# 2_RK3399_SDRAM.net
KiCad netlist of a schematic drawn in Altium Designer
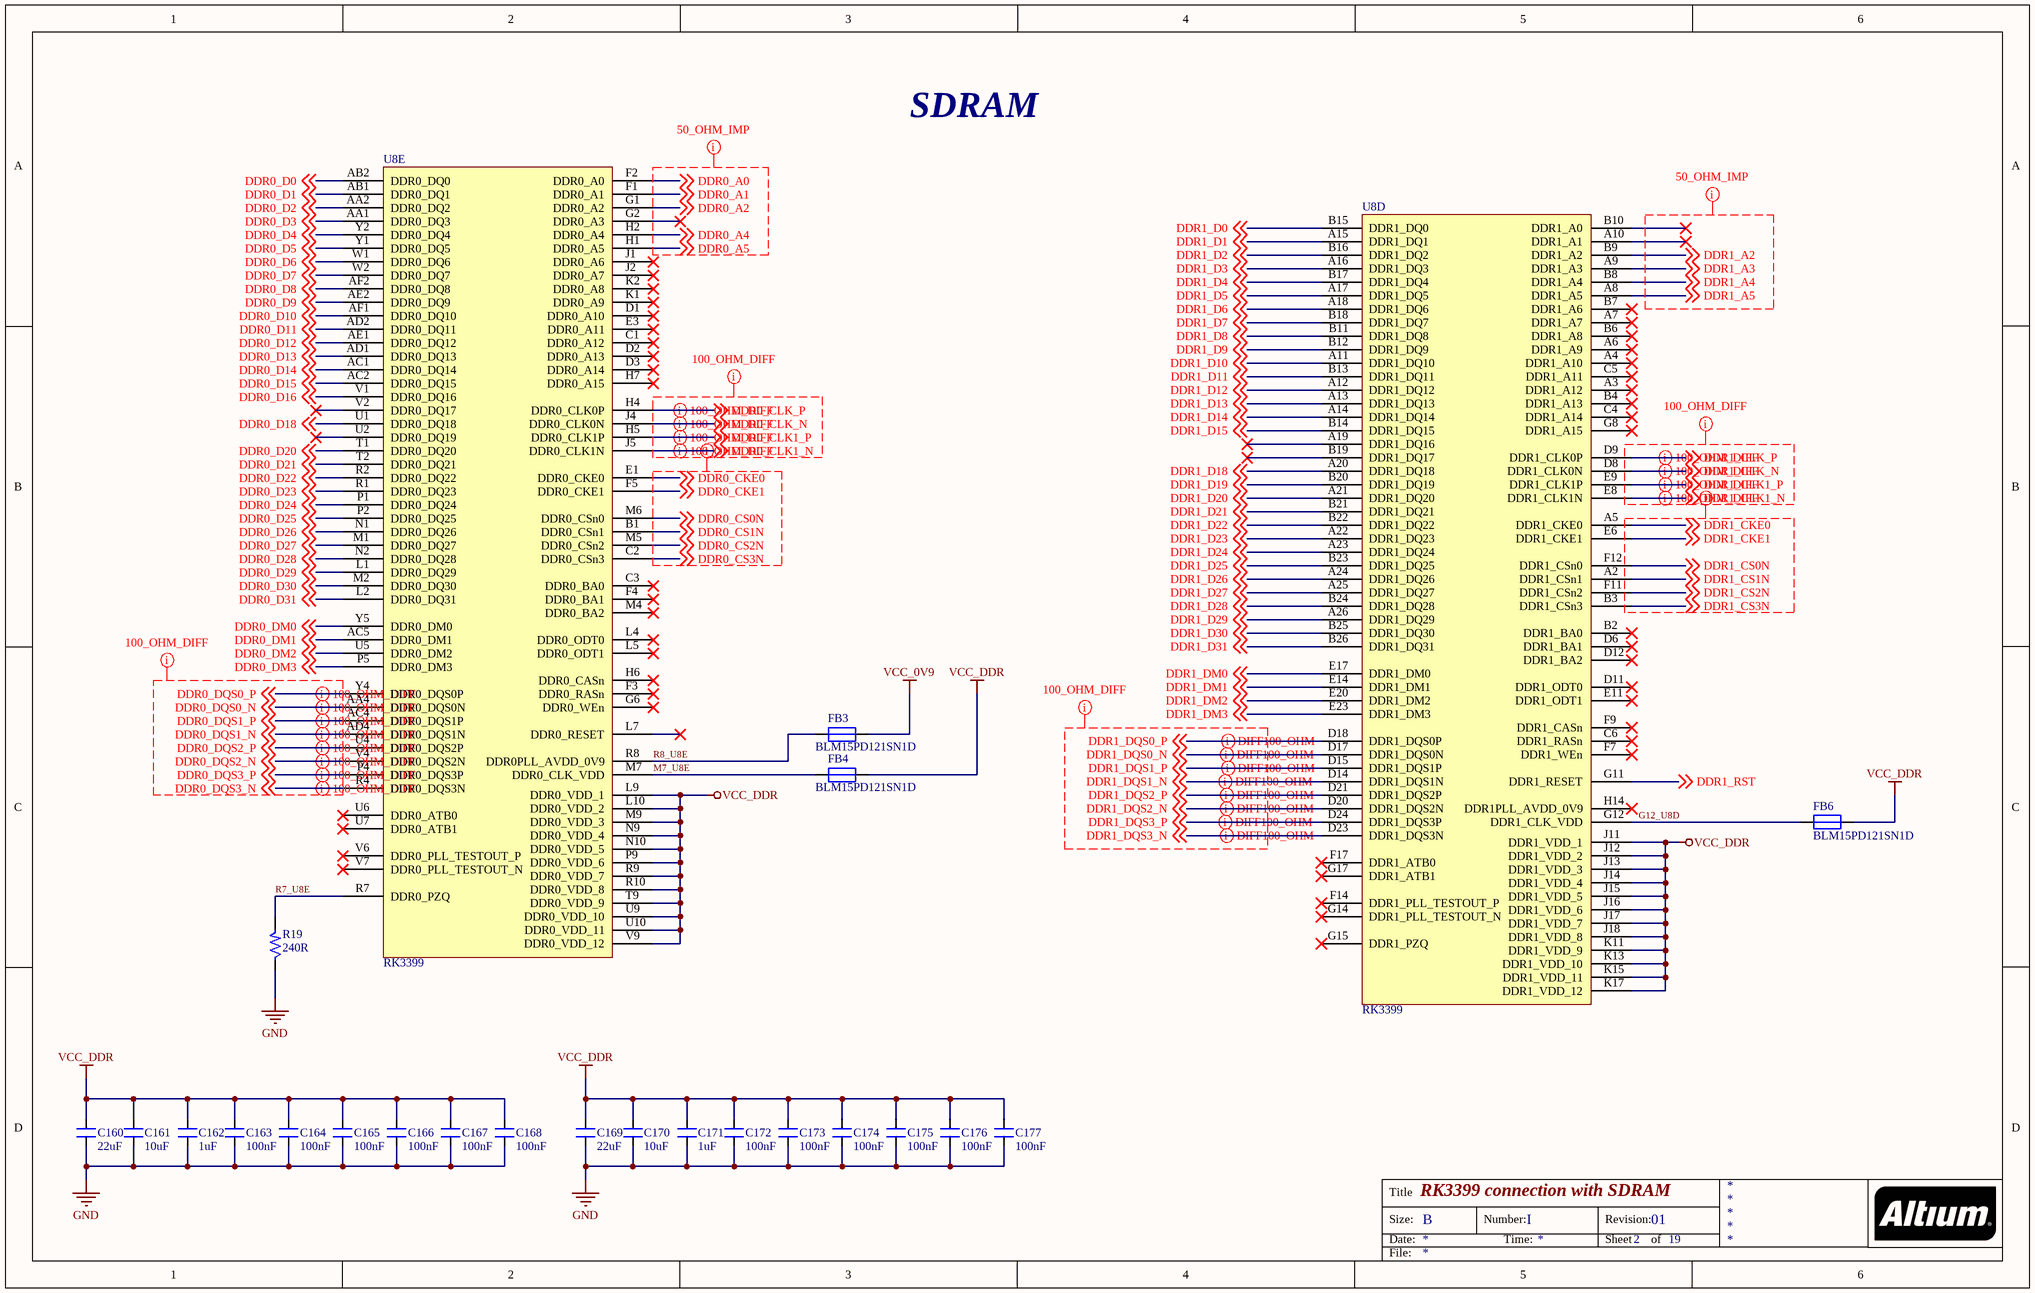
[diagram p0: [2] RK3399_SDRAM.SchDoc]

(export (version "E")
  (design (tool "Eeschema 10.0.6"))
  (components
    (comp (ref "C160")
      (value "22uF")
      (footprint "CAP_0402")
      (description "22µF ±20% 6.3V Ceramic Capacitor X5R 0402 (1005 Metric)")
      (fields
        (field (name "MANUFACTURER") "Murata Electronics")
        (field (name "MANUFACTURER PART NUMBER") "CL05A226MQ5N6J8")
      )
      (libsource (lib "EsteemPCB_SOM_Course_intlib") (part "CAP_22uF-6.3V-20%-0402"))
    )
    (comp (ref "C161")
      (value "10uF")
      (footprint "CAP_0402")
      (description "10µF ±20% 10V Ceramic Capacitor X5R 0402 (1005 Metric)")
      (fields
        (field (name "MANUFACTURER PART NUMBER") "CL05A106MP5NUNC")
        (field (name "MANUFACTURER") "Samsung Electro-Mechanics")
      )
      (libsource (lib "EsteemPCB_SOM_Course_intlib") (part "CAP_10uF-10V-20%-0402"))
    )
    (comp (ref "C162")
      (value "1uF")
      (footprint "CAP_0402")
      (description "1µF ±10% 10V Ceramic Capacitor X6S 0402 (1005 Metric)")
      (fields
        (field (name "MANUFACTURER") "Murata Electronics")
        (field (name "MANUFACTURER PART NUMBER") "GRT155C81A105KE01D")
      )
      (libsource (lib "EsteemPCB_SOM_Course_intlib") (part "CAP_1uF-10V-10%-0402"))
    )
    (comp (ref "C163")
      (value "100nF")
      (footprint "CAP_0402")
      (description "0.1µF ±10% 10V Ceramic Capacitor X7R 0402 (1005 Metric)")
      (fields
        (field (name "MANUFACTURER") "Yageo")
        (field (name "MANUFACTURER PART NUMBER") "CC0402KRX7R6BB104")
      )
      (libsource (lib "EsteemPCB_SOM_Course_intlib") (part "CAP_100nF-10V-10%-0402"))
    )
    (comp (ref "C164")
      (value "100nF")
      (footprint "CAP_0402")
      (description "0.1µF ±10% 10V Ceramic Capacitor X7R 0402 (1005 Metric)")
      (fields
        (field (name "MANUFACTURER") "Yageo")
        (field (name "MANUFACTURER PART NUMBER") "CC0402KRX7R6BB104")
      )
      (libsource (lib "EsteemPCB_SOM_Course_intlib") (part "CAP_100nF-10V-10%-0402"))
    )
    (comp (ref "C165")
      (value "100nF")
      (footprint "CAP_0402")
      (description "0.1µF ±10% 10V Ceramic Capacitor X7R 0402 (1005 Metric)")
      (fields
        (field (name "MANUFACTURER") "Yageo")
        (field (name "MANUFACTURER PART NUMBER") "CC0402KRX7R6BB104")
      )
      (libsource (lib "EsteemPCB_SOM_Course_intlib") (part "CAP_100nF-10V-10%-0402"))
    )
    (comp (ref "C166")
      (value "100nF")
      (footprint "CAP_0402")
      (description "0.1µF ±10% 10V Ceramic Capacitor X7R 0402 (1005 Metric)")
      (fields
        (field (name "MANUFACTURER") "Yageo")
        (field (name "MANUFACTURER PART NUMBER") "CC0402KRX7R6BB104")
      )
      (libsource (lib "EsteemPCB_SOM_Course_intlib") (part "CAP_100nF-10V-10%-0402"))
    )
    (comp (ref "C167")
      (value "100nF")
      (footprint "CAP_0402")
      (description "0.1µF ±10% 10V Ceramic Capacitor X7R 0402 (1005 Metric)")
      (fields
        (field (name "MANUFACTURER") "Yageo")
        (field (name "MANUFACTURER PART NUMBER") "CC0402KRX7R6BB104")
      )
      (libsource (lib "EsteemPCB_SOM_Course_intlib") (part "CAP_100nF-10V-10%-0402"))
    )
    (comp (ref "C168")
      (value "100nF")
      (footprint "CAP_0402")
      (description "0.1µF ±10% 10V Ceramic Capacitor X7R 0402 (1005 Metric)")
      (fields
        (field (name "MANUFACTURER") "Yageo")
        (field (name "MANUFACTURER PART NUMBER") "CC0402KRX7R6BB104")
      )
      (libsource (lib "EsteemPCB_SOM_Course_intlib") (part "CAP_100nF-10V-10%-0402"))
    )
    (comp (ref "C169")
      (value "22uF")
      (footprint "CAP_0402")
      (description "22µF ±20% 6.3V Ceramic Capacitor X5R 0402 (1005 Metric)")
      (fields
        (field (name "MANUFACTURER") "Murata Electronics")
        (field (name "MANUFACTURER PART NUMBER") "CL05A226MQ5N6J8")
      )
      (libsource (lib "EsteemPCB_SOM_Course_intlib") (part "CAP_22uF-6.3V-20%-0402"))
    )
    (comp (ref "C170")
      (value "10uF")
      (footprint "CAP_0402")
      (description "10µF ±20% 10V Ceramic Capacitor X5R 0402 (1005 Metric)")
      (fields
        (field (name "MANUFACTURER PART NUMBER") "CL05A106MP5NUNC")
        (field (name "MANUFACTURER") "Samsung Electro-Mechanics")
      )
      (libsource (lib "EsteemPCB_SOM_Course_intlib") (part "CAP_10uF-10V-20%-0402"))
    )
    (comp (ref "C171")
      (value "1uF")
      (footprint "CAP_0402")
      (description "1µF ±10% 10V Ceramic Capacitor X6S 0402 (1005 Metric)")
      (fields
        (field (name "MANUFACTURER") "Murata Electronics")
        (field (name "MANUFACTURER PART NUMBER") "GRT155C81A105KE01D")
      )
      (libsource (lib "EsteemPCB_SOM_Course_intlib") (part "CAP_1uF-10V-10%-0402"))
    )
    (comp (ref "C172")
      (value "100nF")
      (footprint "CAP_0402")
      (description "0.1µF ±10% 10V Ceramic Capacitor X7R 0402 (1005 Metric)")
      (fields
        (field (name "MANUFACTURER") "Yageo")
        (field (name "MANUFACTURER PART NUMBER") "CC0402KRX7R6BB104")
      )
      (libsource (lib "EsteemPCB_SOM_Course_intlib") (part "CAP_100nF-10V-10%-0402"))
    )
    (comp (ref "C173")
      (value "100nF")
      (footprint "CAP_0402")
      (description "0.1µF ±10% 10V Ceramic Capacitor X7R 0402 (1005 Metric)")
      (fields
        (field (name "MANUFACTURER") "Yageo")
        (field (name "MANUFACTURER PART NUMBER") "CC0402KRX7R6BB104")
      )
      (libsource (lib "EsteemPCB_SOM_Course_intlib") (part "CAP_100nF-10V-10%-0402"))
    )
    (comp (ref "C174")
      (value "100nF")
      (footprint "CAP_0402")
      (description "0.1µF ±10% 10V Ceramic Capacitor X7R 0402 (1005 Metric)")
      (fields
        (field (name "MANUFACTURER") "Yageo")
        (field (name "MANUFACTURER PART NUMBER") "CC0402KRX7R6BB104")
      )
      (libsource (lib "EsteemPCB_SOM_Course_intlib") (part "CAP_100nF-10V-10%-0402"))
    )
    (comp (ref "C175")
      (value "100nF")
      (footprint "CAP_0402")
      (description "0.1µF ±10% 10V Ceramic Capacitor X7R 0402 (1005 Metric)")
      (fields
        (field (name "MANUFACTURER") "Yageo")
        (field (name "MANUFACTURER PART NUMBER") "CC0402KRX7R6BB104")
      )
      (libsource (lib "EsteemPCB_SOM_Course_intlib") (part "CAP_100nF-10V-10%-0402"))
    )
    (comp (ref "C176")
      (value "100nF")
      (footprint "CAP_0402")
      (description "0.1µF ±10% 10V Ceramic Capacitor X7R 0402 (1005 Metric)")
      (fields
        (field (name "MANUFACTURER") "Yageo")
        (field (name "MANUFACTURER PART NUMBER") "CC0402KRX7R6BB104")
      )
      (libsource (lib "EsteemPCB_SOM_Course_intlib") (part "CAP_100nF-10V-10%-0402"))
    )
    (comp (ref "C177")
      (value "100nF")
      (footprint "CAP_0402")
      (description "0.1µF ±10% 10V Ceramic Capacitor X7R 0402 (1005 Metric)")
      (fields
        (field (name "MANUFACTURER") "Yageo")
        (field (name "MANUFACTURER PART NUMBER") "CC0402KRX7R6BB104")
      )
      (libsource (lib "EsteemPCB_SOM_Course_intlib") (part "CAP_100nF-10V-10%-0402"))
    )
    (comp (ref "FB3")
      (value "BLM15PD121SN1D")
      (footprint "RES_0402")
      (description "120 Ohms @ 100MHz 1 Power Line Ferrite Bead 0402 (1005 Metric) 1.3A 90mOhm")
      (fields (field (name "MANUFACTURER") "Murata Electronics"))
      (libsource (lib "EsteemPCB_SOM_Course_intlib") (part "FB_120R-1.3A-100Mhz-0402"))
    )
    (comp (ref "FB4")
      (value "BLM15PD121SN1D")
      (footprint "RES_0402")
      (description "120 Ohms @ 100MHz 1 Power Line Ferrite Bead 0402 (1005 Metric) 1.3A 90mOhm")
      (fields (field (name "MANUFACTURER") "Murata Electronics"))
      (libsource (lib "EsteemPCB_SOM_Course_intlib") (part "FB_120R-1.3A-100Mhz-0402"))
    )
    (comp (ref "FB6")
      (value "BLM15PD121SN1D")
      (footprint "RES_0402")
      (description "120 Ohms @ 100MHz 1 Power Line Ferrite Bead 0402 (1005 Metric) 1.3A 90mOhm")
      (fields (field (name "MANUFACTURER") "Murata Electronics"))
      (libsource (lib "EsteemPCB_SOM_Course_intlib") (part "FB_120R-1.3A-100Mhz-0402"))
    )
    (comp (ref "R19")
      (value "240R")
      (footprint "RES_0201")
      (description "240 Ohms ±1% 0.05W, 1/20W Chip Resistor 0201 (0603 Metric) Thick Film")
      (fields
        (field (name "MANUFACTURER") "Yageo")
        (field (name "MANUFACTURER PART NUMBER") "RC0201FR-07240RL")
      )
      (libsource (lib "EsteemPCB_SOM_Course_intlib") (part "RES_240R-0.05W-1%-0201"))
    )
    (comp (ref "U8")
      (value "RK3399")
      (footprint "FBGA828_23_826X826")
      (description "RK3399 is a low power, high performance processor for computing, personal mobile.")
      (fields (field (name "MANUFACTURER") "Rockchip"))
      (libsource (lib "EsteemPCB_SOM_Course_intlib") (part "IC_RK3399-FCBGA828"))
    )
  )
  (nets
    (net (code "1") (name "/G12_U8D") (class "Default")
      (node (ref "FB6") (pin "1") (pinfunction "1_1") (pintype "passive"))
      (node (ref "U8") (pin "G12") (pinfunction "DDR1_CLK_VDD_G12") (pintype "passive"))
    )
    (net (code "2") (name "/M7_U8E") (class "Default")
      (node (ref "FB4") (pin "1") (pinfunction "1_1") (pintype "passive"))
      (node (ref "U8") (pin "M7") (pinfunction "DDR0_CLK_VDD_M7") (pintype "passive"))
    )
    (net (code "3") (name "/R7_U8E") (class "Default")
      (node (ref "R19") (pin "2") (pinfunction "2_2") (pintype "passive"))
      (node (ref "U8") (pin "R7") (pinfunction "DDR0_PZQ_R7") (pintype "passive"))
    )
    (net (code "4") (name "/R8_U8E") (class "Default")
      (node (ref "FB3") (pin "1") (pinfunction "1_1") (pintype "passive"))
      (node (ref "U8") (pin "R8") (pinfunction "DDR0PLL_AVDD_0V9_R8") (pintype "passive"))
    )
    (net (code "5") (name "DDR0_A0") (class "Default")
      (node (ref "U8") (pin "F2") (pinfunction "DDR0_A0_F2") (pintype "passive"))
    )
    (net (code "6") (name "DDR0_A1") (class "Default")
      (node (ref "U8") (pin "F1") (pinfunction "DDR0_A1_F1") (pintype "passive"))
    )
    (net (code "7") (name "DDR0_A2") (class "Default")
      (node (ref "U8") (pin "G1") (pinfunction "DDR0_A2_G1") (pintype "passive"))
    )
    (net (code "8") (name "DDR0_A4") (class "Default")
      (node (ref "U8") (pin "H2") (pinfunction "DDR0_A4_H2") (pintype "passive"))
    )
    (net (code "9") (name "DDR0_A5") (class "Default")
      (node (ref "U8") (pin "H1") (pinfunction "DDR0_A5_H1") (pintype "passive"))
    )
    (net (code "10") (name "DDR0_CKE0") (class "Default")
      (node (ref "U8") (pin "E1") (pinfunction "DDR0_CKE0_E1") (pintype "passive"))
    )
    (net (code "11") (name "DDR0_CKE1") (class "Default")
      (node (ref "U8") (pin "F5") (pinfunction "DDR0_CKE1_F5") (pintype "passive"))
    )
    (net (code "12") (name "DDR0_CLK1_N") (class "Default")
      (node (ref "U8") (pin "J5") (pinfunction "DDR0_CLK1N_J5") (pintype "passive"))
    )
    (net (code "13") (name "DDR0_CLK1_P") (class "Default")
      (node (ref "U8") (pin "H5") (pinfunction "DDR0_CLK1P_H5") (pintype "passive"))
    )
    (net (code "14") (name "DDR0_CLK_N") (class "Default")
      (node (ref "U8") (pin "J4") (pinfunction "DDR0_CLK0N_J4") (pintype "passive"))
    )
    (net (code "15") (name "DDR0_CLK_P") (class "Default")
      (node (ref "U8") (pin "H4") (pinfunction "DDR0_CLK0P_H4") (pintype "passive"))
    )
    (net (code "16") (name "DDR0_CS0N") (class "Default")
      (node (ref "U8") (pin "M6") (pinfunction "DDR0_CSn0_M6") (pintype "passive"))
    )
    (net (code "17") (name "DDR0_CS1N") (class "Default")
      (node (ref "U8") (pin "B1") (pinfunction "DDR0_CSn1_B1") (pintype "passive"))
    )
    (net (code "18") (name "DDR0_CS2N") (class "Default")
      (node (ref "U8") (pin "M5") (pinfunction "DDR0_CSn2_M5") (pintype "passive"))
    )
    (net (code "19") (name "DDR0_CS3N") (class "Default")
      (node (ref "U8") (pin "C2") (pinfunction "DDR0_CSn3_C2") (pintype "passive"))
    )
    (net (code "20") (name "DDR0_D0") (class "Default")
      (node (ref "U8") (pin "AB2") (pinfunction "DDR0_DQ0_AB2") (pintype "passive"))
    )
    (net (code "21") (name "DDR0_D1") (class "Default")
      (node (ref "U8") (pin "AB1") (pinfunction "DDR0_DQ1_AB1") (pintype "passive"))
    )
    (net (code "22") (name "DDR0_D2") (class "Default")
      (node (ref "U8") (pin "AA2") (pinfunction "DDR0_DQ2_AA2") (pintype "passive"))
    )
    (net (code "23") (name "DDR0_D3") (class "Default")
      (node (ref "U8") (pin "AA1") (pinfunction "DDR0_DQ3_AA1") (pintype "passive"))
    )
    (net (code "24") (name "DDR0_D4") (class "Default")
      (node (ref "U8") (pin "Y2") (pinfunction "DDR0_DQ4_Y2") (pintype "passive"))
    )
    (net (code "25") (name "DDR0_D5") (class "Default")
      (node (ref "U8") (pin "Y1") (pinfunction "DDR0_DQ5_Y1") (pintype "passive"))
    )
    (net (code "26") (name "DDR0_D6") (class "Default")
      (node (ref "U8") (pin "W1") (pinfunction "DDR0_DQ6_W1") (pintype "passive"))
    )
    (net (code "27") (name "DDR0_D7") (class "Default")
      (node (ref "U8") (pin "W2") (pinfunction "DDR0_DQ7_W2") (pintype "passive"))
    )
    (net (code "28") (name "DDR0_D8") (class "Default")
      (node (ref "U8") (pin "AF2") (pinfunction "DDR0_DQ8_AF2") (pintype "passive"))
    )
    (net (code "29") (name "DDR0_D9") (class "Default")
      (node (ref "U8") (pin "AE2") (pinfunction "DDR0_DQ9_AE2") (pintype "passive"))
    )
    (net (code "30") (name "DDR0_D10") (class "Default")
      (node (ref "U8") (pin "AF1") (pinfunction "DDR0_DQ10_AF1") (pintype "passive"))
    )
    (net (code "31") (name "DDR0_D11") (class "Default")
      (node (ref "U8") (pin "AD2") (pinfunction "DDR0_DQ11_AD2") (pintype "passive"))
    )
    (net (code "32") (name "DDR0_D12") (class "Default")
      (node (ref "U8") (pin "AE1") (pinfunction "DDR0_DQ12_AE1") (pintype "passive"))
    )
    (net (code "33") (name "DDR0_D13") (class "Default")
      (node (ref "U8") (pin "AD1") (pinfunction "DDR0_DQ13_AD1") (pintype "passive"))
    )
    (net (code "34") (name "DDR0_D14") (class "Default")
      (node (ref "U8") (pin "AC1") (pinfunction "DDR0_DQ14_AC1") (pintype "passive"))
    )
    (net (code "35") (name "DDR0_D15") (class "Default")
      (node (ref "U8") (pin "AC2") (pinfunction "DDR0_DQ15_AC2") (pintype "passive"))
    )
    (net (code "36") (name "DDR0_D16") (class "Default")
      (node (ref "U8") (pin "V1") (pinfunction "DDR0_DQ16_V1") (pintype "passive"))
    )
    (net (code "37") (name "DDR0_D18") (class "Default")
      (node (ref "U8") (pin "U1") (pinfunction "DDR0_DQ18_U1") (pintype "passive"))
    )
    (net (code "38") (name "DDR0_D20") (class "Default")
      (node (ref "U8") (pin "T1") (pinfunction "DDR0_DQ20_T1") (pintype "passive"))
    )
    (net (code "39") (name "DDR0_D21") (class "Default")
      (node (ref "U8") (pin "T2") (pinfunction "DDR0_DQ21_T2") (pintype "passive"))
    )
    (net (code "40") (name "DDR0_D22") (class "Default")
      (node (ref "U8") (pin "R2") (pinfunction "DDR0_DQ22_R2") (pintype "passive"))
    )
    (net (code "41") (name "DDR0_D23") (class "Default")
      (node (ref "U8") (pin "R1") (pinfunction "DDR0_DQ23_R1") (pintype "passive"))
    )
    (net (code "42") (name "DDR0_D24") (class "Default")
      (node (ref "U8") (pin "P1") (pinfunction "DDR0_DQ24_P1") (pintype "passive"))
    )
    (net (code "43") (name "DDR0_D25") (class "Default")
      (node (ref "U8") (pin "P2") (pinfunction "DDR0_DQ25_P2") (pintype "passive"))
    )
    (net (code "44") (name "DDR0_D26") (class "Default")
      (node (ref "U8") (pin "N1") (pinfunction "DDR0_DQ26_N1") (pintype "passive"))
    )
    (net (code "45") (name "DDR0_D27") (class "Default")
      (node (ref "U8") (pin "M1") (pinfunction "DDR0_DQ27_M1") (pintype "passive"))
    )
    (net (code "46") (name "DDR0_D28") (class "Default")
      (node (ref "U8") (pin "N2") (pinfunction "DDR0_DQ28_N2") (pintype "passive"))
    )
    (net (code "47") (name "DDR0_D29") (class "Default")
      (node (ref "U8") (pin "L1") (pinfunction "DDR0_DQ29_L1") (pintype "passive"))
    )
    (net (code "48") (name "DDR0_D30") (class "Default")
      (node (ref "U8") (pin "M2") (pinfunction "DDR0_DQ30_M2") (pintype "passive"))
    )
    (net (code "49") (name "DDR0_D31") (class "Default")
      (node (ref "U8") (pin "L2") (pinfunction "DDR0_DQ31_L2") (pintype "passive"))
    )
    (net (code "50") (name "DDR0_DM0") (class "Default")
      (node (ref "U8") (pin "Y5") (pinfunction "DDR0_DM0_Y5") (pintype "passive"))
    )
    (net (code "51") (name "DDR0_DM1") (class "Default")
      (node (ref "U8") (pin "AC5") (pinfunction "DDR0_DM1_AC5") (pintype "passive"))
    )
    (net (code "52") (name "DDR0_DM2") (class "Default")
      (node (ref "U8") (pin "U5") (pinfunction "DDR0_DM2_U5") (pintype "passive"))
    )
    (net (code "53") (name "DDR0_DM3") (class "Default")
      (node (ref "U8") (pin "P5") (pinfunction "DDR0_DM3_P5") (pintype "passive"))
    )
    (net (code "54") (name "DDR0_DQS0_N") (class "Default")
      (node (ref "U8") (pin "AA4") (pinfunction "DDR0_DQS0N_AA4") (pintype "passive"))
    )
    (net (code "55") (name "DDR0_DQS0_P") (class "Default")
      (node (ref "U8") (pin "Y4") (pinfunction "DDR0_DQS0P_Y4") (pintype "passive"))
    )
    (net (code "56") (name "DDR0_DQS1_N") (class "Default")
      (node (ref "U8") (pin "AD4") (pinfunction "DDR0_DQS1N_AD4") (pintype "passive"))
    )
    (net (code "57") (name "DDR0_DQS1_P") (class "Default")
      (node (ref "U8") (pin "AC4") (pinfunction "DDR0_DQS1P_AC4") (pintype "passive"))
    )
    (net (code "58") (name "DDR0_DQS2_N") (class "Default")
      (node (ref "U8") (pin "V4") (pinfunction "DDR0_DQS2N_V4") (pintype "passive"))
    )
    (net (code "59") (name "DDR0_DQS2_P") (class "Default")
      (node (ref "U8") (pin "U4") (pinfunction "DDR0_DQS2P_U4") (pintype "passive"))
    )
    (net (code "60") (name "DDR0_DQS3_N") (class "Default")
      (node (ref "U8") (pin "R4") (pinfunction "DDR0_DQS3N_R4") (pintype "passive"))
    )
    (net (code "61") (name "DDR0_DQS3_P") (class "Default")
      (node (ref "U8") (pin "P4") (pinfunction "DDR0_DQS3P_P4") (pintype "passive"))
    )
    (net (code "62") (name "DDR1_A2") (class "Default")
      (node (ref "U8") (pin "B9") (pinfunction "DDR1_A2_B9") (pintype "passive"))
    )
    (net (code "63") (name "DDR1_A3") (class "Default")
      (node (ref "U8") (pin "A9") (pinfunction "DDR1_A3_A9") (pintype "passive"))
    )
    (net (code "64") (name "DDR1_A4") (class "Default")
      (node (ref "U8") (pin "B8") (pinfunction "DDR1_A4_B8") (pintype "passive"))
    )
    (net (code "65") (name "DDR1_A5") (class "Default")
      (node (ref "U8") (pin "A8") (pinfunction "DDR1_A5_A8") (pintype "passive"))
    )
    (net (code "66") (name "DDR1_CKE0") (class "Default")
      (node (ref "U8") (pin "A5") (pinfunction "DDR1_CKE0_A5") (pintype "passive"))
    )
    (net (code "67") (name "DDR1_CKE1") (class "Default")
      (node (ref "U8") (pin "E6") (pinfunction "DDR1_CKE1_E6") (pintype "passive"))
    )
    (net (code "68") (name "DDR1_CLK1_N") (class "Default")
      (node (ref "U8") (pin "E8") (pinfunction "DDR1_CLK1N_E8") (pintype "passive"))
    )
    (net (code "69") (name "DDR1_CLK1_P") (class "Default")
      (node (ref "U8") (pin "E9") (pinfunction "DDR1_CLK1P_E9") (pintype "passive"))
    )
    (net (code "70") (name "DDR1_CLK_N") (class "Default")
      (node (ref "U8") (pin "D8") (pinfunction "DDR1_CLK0N_D8") (pintype "passive"))
    )
    (net (code "71") (name "DDR1_CLK_P") (class "Default")
      (node (ref "U8") (pin "D9") (pinfunction "DDR1_CLK0P_D9") (pintype "passive"))
    )
    (net (code "72") (name "DDR1_CS0N") (class "Default")
      (node (ref "U8") (pin "F12") (pinfunction "DDR1_CSn0_F12") (pintype "passive"))
    )
    (net (code "73") (name "DDR1_CS1N") (class "Default")
      (node (ref "U8") (pin "A2") (pinfunction "DDR1_CSn1_A2") (pintype "passive"))
    )
    (net (code "74") (name "DDR1_CS2N") (class "Default")
      (node (ref "U8") (pin "F11") (pinfunction "DDR1_CSn2_F11") (pintype "passive"))
    )
    (net (code "75") (name "DDR1_CS3N") (class "Default")
      (node (ref "U8") (pin "B3") (pinfunction "DDR1_CSn3_B3") (pintype "passive"))
    )
    (net (code "76") (name "DDR1_D0") (class "Default")
      (node (ref "U8") (pin "B15") (pinfunction "DDR1_DQ0_B15") (pintype "passive"))
    )
    (net (code "77") (name "DDR1_D1") (class "Default")
      (node (ref "U8") (pin "A15") (pinfunction "DDR1_DQ1_A15") (pintype "passive"))
    )
    (net (code "78") (name "DDR1_D2") (class "Default")
      (node (ref "U8") (pin "B16") (pinfunction "DDR1_DQ2_B16") (pintype "passive"))
    )
    (net (code "79") (name "DDR1_D3") (class "Default")
      (node (ref "U8") (pin "A16") (pinfunction "DDR1_DQ3_A16") (pintype "passive"))
    )
    (net (code "80") (name "DDR1_D4") (class "Default")
      (node (ref "U8") (pin "B17") (pinfunction "DDR1_DQ4_B17") (pintype "passive"))
    )
    (net (code "81") (name "DDR1_D5") (class "Default")
      (node (ref "U8") (pin "A17") (pinfunction "DDR1_DQ5_A17") (pintype "passive"))
    )
    (net (code "82") (name "DDR1_D6") (class "Default")
      (node (ref "U8") (pin "A18") (pinfunction "DDR1_DQ6_A18") (pintype "passive"))
    )
    (net (code "83") (name "DDR1_D7") (class "Default")
      (node (ref "U8") (pin "B18") (pinfunction "DDR1_DQ7_B18") (pintype "passive"))
    )
    (net (code "84") (name "DDR1_D8") (class "Default")
      (node (ref "U8") (pin "B11") (pinfunction "DDR1_DQ8_B11") (pintype "passive"))
    )
    (net (code "85") (name "DDR1_D9") (class "Default")
      (node (ref "U8") (pin "B12") (pinfunction "DDR1_DQ9_B12") (pintype "passive"))
    )
    (net (code "86") (name "DDR1_D10") (class "Default")
      (node (ref "U8") (pin "A11") (pinfunction "DDR1_DQ10_A11") (pintype "passive"))
    )
    (net (code "87") (name "DDR1_D11") (class "Default")
      (node (ref "U8") (pin "B13") (pinfunction "DDR1_DQ11_B13") (pintype "passive"))
    )
    (net (code "88") (name "DDR1_D12") (class "Default")
      (node (ref "U8") (pin "A12") (pinfunction "DDR1_DQ12_A12") (pintype "passive"))
    )
    (net (code "89") (name "DDR1_D13") (class "Default")
      (node (ref "U8") (pin "A13") (pinfunction "DDR1_DQ13_A13") (pintype "passive"))
    )
    (net (code "90") (name "DDR1_D14") (class "Default")
      (node (ref "U8") (pin "A14") (pinfunction "DDR1_DQ14_A14") (pintype "passive"))
    )
    (net (code "91") (name "DDR1_D15") (class "Default")
      (node (ref "U8") (pin "B14") (pinfunction "DDR1_DQ15_B14") (pintype "passive"))
    )
    (net (code "92") (name "DDR1_D18") (class "Default")
      (node (ref "U8") (pin "A20") (pinfunction "DDR1_DQ18_A20") (pintype "passive"))
    )
    (net (code "93") (name "DDR1_D19") (class "Default")
      (node (ref "U8") (pin "B20") (pinfunction "DDR1_DQ19_B20") (pintype "passive"))
    )
    (net (code "94") (name "DDR1_D20") (class "Default")
      (node (ref "U8") (pin "A21") (pinfunction "DDR1_DQ20_A21") (pintype "passive"))
    )
    (net (code "95") (name "DDR1_D21") (class "Default")
      (node (ref "U8") (pin "B21") (pinfunction "DDR1_DQ21_B21") (pintype "passive"))
    )
    (net (code "96") (name "DDR1_D22") (class "Default")
      (node (ref "U8") (pin "B22") (pinfunction "DDR1_DQ22_B22") (pintype "passive"))
    )
    (net (code "97") (name "DDR1_D23") (class "Default")
      (node (ref "U8") (pin "A22") (pinfunction "DDR1_DQ23_A22") (pintype "passive"))
    )
    (net (code "98") (name "DDR1_D24") (class "Default")
      (node (ref "U8") (pin "A23") (pinfunction "DDR1_DQ24_A23") (pintype "passive"))
    )
    (net (code "99") (name "DDR1_D25") (class "Default")
      (node (ref "U8") (pin "B23") (pinfunction "DDR1_DQ25_B23") (pintype "passive"))
    )
    (net (code "100") (name "DDR1_D26") (class "Default")
      (node (ref "U8") (pin "A24") (pinfunction "DDR1_DQ26_A24") (pintype "passive"))
    )
    (net (code "101") (name "DDR1_D27") (class "Default")
      (node (ref "U8") (pin "A25") (pinfunction "DDR1_DQ27_A25") (pintype "passive"))
    )
    (net (code "102") (name "DDR1_D28") (class "Default")
      (node (ref "U8") (pin "B24") (pinfunction "DDR1_DQ28_B24") (pintype "passive"))
    )
    (net (code "103") (name "DDR1_D29") (class "Default")
      (node (ref "U8") (pin "A26") (pinfunction "DDR1_DQ29_A26") (pintype "passive"))
    )
    (net (code "104") (name "DDR1_D30") (class "Default")
      (node (ref "U8") (pin "B25") (pinfunction "DDR1_DQ30_B25") (pintype "passive"))
    )
    (net (code "105") (name "DDR1_D31") (class "Default")
      (node (ref "U8") (pin "B26") (pinfunction "DDR1_DQ31_B26") (pintype "passive"))
    )
    (net (code "106") (name "DDR1_DM0") (class "Default")
      (node (ref "U8") (pin "E17") (pinfunction "DDR1_DM0_E17") (pintype "passive"))
    )
    (net (code "107") (name "DDR1_DM1") (class "Default")
      (node (ref "U8") (pin "E14") (pinfunction "DDR1_DM1_E14") (pintype "passive"))
    )
    (net (code "108") (name "DDR1_DM2") (class "Default")
      (node (ref "U8") (pin "E20") (pinfunction "DDR1_DM2_E20") (pintype "passive"))
    )
    (net (code "109") (name "DDR1_DM3") (class "Default")
      (node (ref "U8") (pin "E23") (pinfunction "DDR1_DM3_E23") (pintype "passive"))
    )
    (net (code "110") (name "DDR1_DQS0_N") (class "Default")
      (node (ref "U8") (pin "D17") (pinfunction "DDR1_DQS0N_D17") (pintype "passive"))
    )
    (net (code "111") (name "DDR1_DQS0_P") (class "Default")
      (node (ref "U8") (pin "D18") (pinfunction "DDR1_DQS0P_D18") (pintype "passive"))
    )
    (net (code "112") (name "DDR1_DQS1_N") (class "Default")
      (node (ref "U8") (pin "D14") (pinfunction "DDR1_DQS1N_D14") (pintype "passive"))
    )
    (net (code "113") (name "DDR1_DQS1_P") (class "Default")
      (node (ref "U8") (pin "D15") (pinfunction "DDR1_DQS1P_D15") (pintype "passive"))
    )
    (net (code "114") (name "DDR1_DQS2_N") (class "Default")
      (node (ref "U8") (pin "D20") (pinfunction "DDR1_DQS2N_D20") (pintype "passive"))
    )
    (net (code "115") (name "DDR1_DQS2_P") (class "Default")
      (node (ref "U8") (pin "D21") (pinfunction "DDR1_DQS2P_D21") (pintype "passive"))
    )
    (net (code "116") (name "DDR1_DQS3_N") (class "Default")
      (node (ref "U8") (pin "D23") (pinfunction "DDR1_DQS3N_D23") (pintype "passive"))
    )
    (net (code "117") (name "DDR1_DQS3_P") (class "Default")
      (node (ref "U8") (pin "D24") (pinfunction "DDR1_DQS3P_D24") (pintype "passive"))
    )
    (net (code "118") (name "DDR1_RST") (class "Default")
      (node (ref "U8") (pin "G11") (pinfunction "DDR1_RESET_G11") (pintype "passive"))
    )
    (net (code "119") (name "GND") (class "Default")
      (node (ref "C160") (pin "1") (pinfunction "1_1") (pintype "passive"))
      (node (ref "C161") (pin "1") (pinfunction "1_1") (pintype "passive"))
      (node (ref "C162") (pin "1") (pinfunction "1_1") (pintype "passive"))
      (node (ref "C163") (pin "1") (pinfunction "1_1") (pintype "passive"))
      (node (ref "C164") (pin "1") (pinfunction "1_1") (pintype "passive"))
      (node (ref "C165") (pin "1") (pinfunction "1_1") (pintype "passive"))
      (node (ref "C166") (pin "1") (pinfunction "1_1") (pintype "passive"))
      (node (ref "C167") (pin "1") (pinfunction "1_1") (pintype "passive"))
      (node (ref "C168") (pin "1") (pinfunction "1_1") (pintype "passive"))
      (node (ref "C169") (pin "1") (pinfunction "1_1") (pintype "passive"))
      (node (ref "C170") (pin "1") (pinfunction "1_1") (pintype "passive"))
      (node (ref "C171") (pin "1") (pinfunction "1_1") (pintype "passive"))
      (node (ref "C172") (pin "1") (pinfunction "1_1") (pintype "passive"))
      (node (ref "C173") (pin "1") (pinfunction "1_1") (pintype "passive"))
      (node (ref "C174") (pin "1") (pinfunction "1_1") (pintype "passive"))
      (node (ref "C175") (pin "1") (pinfunction "1_1") (pintype "passive"))
      (node (ref "C176") (pin "1") (pinfunction "1_1") (pintype "passive"))
      (node (ref "C177") (pin "1") (pinfunction "1_1") (pintype "passive"))
      (node (ref "R19") (pin "1") (pinfunction "1_1") (pintype "passive"))
    )
    (net (code "120") (name "VCC_0V9") (class "Default")
      (node (ref "FB3") (pin "2") (pinfunction "2_2") (pintype "passive"))
    )
    (net (code "121") (name "VCC_DDR") (class "Default")
      (node (ref "C160") (pin "2") (pinfunction "2_2") (pintype "passive"))
      (node (ref "C161") (pin "2") (pinfunction "2_2") (pintype "passive"))
      (node (ref "C162") (pin "2") (pinfunction "2_2") (pintype "passive"))
      (node (ref "C163") (pin "2") (pinfunction "2_2") (pintype "passive"))
      (node (ref "C164") (pin "2") (pinfunction "2_2") (pintype "passive"))
      (node (ref "C165") (pin "2") (pinfunction "2_2") (pintype "passive"))
      (node (ref "C166") (pin "2") (pinfunction "2_2") (pintype "passive"))
      (node (ref "C167") (pin "2") (pinfunction "2_2") (pintype "passive"))
      (node (ref "C168") (pin "2") (pinfunction "2_2") (pintype "passive"))
      (node (ref "C169") (pin "2") (pinfunction "2_2") (pintype "passive"))
      (node (ref "C170") (pin "2") (pinfunction "2_2") (pintype "passive"))
      (node (ref "C171") (pin "2") (pinfunction "2_2") (pintype "passive"))
      (node (ref "C172") (pin "2") (pinfunction "2_2") (pintype "passive"))
      (node (ref "C173") (pin "2") (pinfunction "2_2") (pintype "passive"))
      (node (ref "C174") (pin "2") (pinfunction "2_2") (pintype "passive"))
      (node (ref "C175") (pin "2") (pinfunction "2_2") (pintype "passive"))
      (node (ref "C176") (pin "2") (pinfunction "2_2") (pintype "passive"))
      (node (ref "C177") (pin "2") (pinfunction "2_2") (pintype "passive"))
      (node (ref "FB4") (pin "2") (pinfunction "2_2") (pintype "passive"))
      (node (ref "FB6") (pin "2") (pinfunction "2_2") (pintype "passive"))
      (node (ref "U8") (pin "J11") (pinfunction "DDR1_VDD_1_J11") (pintype "passive"))
      (node (ref "U8") (pin "J12") (pinfunction "DDR1_VDD_2_J12") (pintype "passive"))
      (node (ref "U8") (pin "J13") (pinfunction "DDR1_VDD_3_J13") (pintype "passive"))
      (node (ref "U8") (pin "J14") (pinfunction "DDR1_VDD_4_J14") (pintype "passive"))
      (node (ref "U8") (pin "J15") (pinfunction "DDR1_VDD_5_J15") (pintype "passive"))
      (node (ref "U8") (pin "J16") (pinfunction "DDR1_VDD_6_J16") (pintype "passive"))
      (node (ref "U8") (pin "J17") (pinfunction "DDR1_VDD_7_J17") (pintype "passive"))
      (node (ref "U8") (pin "J18") (pinfunction "DDR1_VDD_8_J18") (pintype "passive"))
      (node (ref "U8") (pin "K11") (pinfunction "DDR1_VDD_9_K11") (pintype "passive"))
      (node (ref "U8") (pin "K13") (pinfunction "DDR1_VDD_10_K13") (pintype "passive"))
      (node (ref "U8") (pin "K15") (pinfunction "DDR1_VDD_11_K15") (pintype "passive"))
      (node (ref "U8") (pin "K17") (pinfunction "DDR1_VDD_12_K17") (pintype "passive"))
      (node (ref "U8") (pin "L10") (pinfunction "DDR0_VDD_2_L10") (pintype "passive"))
      (node (ref "U8") (pin "L9") (pinfunction "DDR0_VDD_1_L9") (pintype "passive"))
      (node (ref "U8") (pin "M9") (pinfunction "DDR0_VDD_3_M9") (pintype "passive"))
      (node (ref "U8") (pin "N10") (pinfunction "DDR0_VDD_5_N10") (pintype "passive"))
      (node (ref "U8") (pin "N9") (pinfunction "DDR0_VDD_4_N9") (pintype "passive"))
      (node (ref "U8") (pin "P9") (pinfunction "DDR0_VDD_6_P9") (pintype "passive"))
      (node (ref "U8") (pin "R10") (pinfunction "DDR0_VDD_8_R10") (pintype "passive"))
      (node (ref "U8") (pin "R9") (pinfunction "DDR0_VDD_7_R9") (pintype "passive"))
      (node (ref "U8") (pin "T9") (pinfunction "DDR0_VDD_9_T9") (pintype "passive"))
      (node (ref "U8") (pin "U10") (pinfunction "DDR0_VDD_11_U10") (pintype "passive"))
      (node (ref "U8") (pin "U9") (pinfunction "DDR0_VDD_10_U9") (pintype "passive"))
      (node (ref "U8") (pin "V9") (pinfunction "DDR0_VDD_12_V9") (pintype "passive"))
    )
    (net (code "122") (name "unconnected-(U8D-DDR1PLL_AVDD_0V9-PadH14)") (class "Default")
      (node (ref "U8") (pin "H14") (pinfunction "DDR1PLL_AVDD_0V9_H14") (pintype "passive+no_connect"))
    )
    (net (code "123") (name "unconnected-(U8D-DDR1_A0-PadB10)") (class "Default")
      (node (ref "U8") (pin "B10") (pinfunction "DDR1_A0_B10") (pintype "passive+no_connect"))
    )
    (net (code "124") (name "unconnected-(U8D-DDR1_A1-PadA10)") (class "Default")
      (node (ref "U8") (pin "A10") (pinfunction "DDR1_A1_A10") (pintype "passive+no_connect"))
    )
    (net (code "125") (name "unconnected-(U8D-DDR1_A6-PadB7)") (class "Default")
      (node (ref "U8") (pin "B7") (pinfunction "DDR1_A6_B7") (pintype "passive+no_connect"))
    )
    (net (code "126") (name "unconnected-(U8D-DDR1_A7-PadA7)") (class "Default")
      (node (ref "U8") (pin "A7") (pinfunction "DDR1_A7_A7") (pintype "passive+no_connect"))
    )
    (net (code "127") (name "unconnected-(U8D-DDR1_A8-PadB6)") (class "Default")
      (node (ref "U8") (pin "B6") (pinfunction "DDR1_A8_B6") (pintype "passive+no_connect"))
    )
    (net (code "128") (name "unconnected-(U8D-DDR1_A9-PadA6)") (class "Default")
      (node (ref "U8") (pin "A6") (pinfunction "DDR1_A9_A6") (pintype "passive+no_connect"))
    )
    (net (code "129") (name "unconnected-(U8D-DDR1_A10-PadA4)") (class "Default")
      (node (ref "U8") (pin "A4") (pinfunction "DDR1_A10_A4") (pintype "passive+no_connect"))
    )
    (net (code "130") (name "unconnected-(U8D-DDR1_A11-PadC5)") (class "Default")
      (node (ref "U8") (pin "C5") (pinfunction "DDR1_A11_C5") (pintype "passive+no_connect"))
    )
    (net (code "131") (name "unconnected-(U8D-DDR1_A12-PadA3)") (class "Default")
      (node (ref "U8") (pin "A3") (pinfunction "DDR1_A12_A3") (pintype "passive+no_connect"))
    )
    (net (code "132") (name "unconnected-(U8D-DDR1_A13-PadB4)") (class "Default")
      (node (ref "U8") (pin "B4") (pinfunction "DDR1_A13_B4") (pintype "passive+no_connect"))
    )
    (net (code "133") (name "unconnected-(U8D-DDR1_A14-PadC4)") (class "Default")
      (node (ref "U8") (pin "C4") (pinfunction "DDR1_A14_C4") (pintype "passive+no_connect"))
    )
    (net (code "134") (name "unconnected-(U8D-DDR1_A15-PadG8)") (class "Default")
      (node (ref "U8") (pin "G8") (pinfunction "DDR1_A15_G8") (pintype "passive+no_connect"))
    )
    (net (code "135") (name "unconnected-(U8D-DDR1_ATB0-PadF17)") (class "Default")
      (node (ref "U8") (pin "F17") (pinfunction "DDR1_ATB0_F17") (pintype "passive+no_connect"))
    )
    (net (code "136") (name "unconnected-(U8D-DDR1_ATB1-PadG17)") (class "Default")
      (node (ref "U8") (pin "G17") (pinfunction "DDR1_ATB1_G17") (pintype "passive+no_connect"))
    )
    (net (code "137") (name "unconnected-(U8D-DDR1_BA0-PadB2)") (class "Default")
      (node (ref "U8") (pin "B2") (pinfunction "DDR1_BA0_B2") (pintype "passive+no_connect"))
    )
    (net (code "138") (name "unconnected-(U8D-DDR1_BA1-PadD6)") (class "Default")
      (node (ref "U8") (pin "D6") (pinfunction "DDR1_BA1_D6") (pintype "passive+no_connect"))
    )
    (net (code "139") (name "unconnected-(U8D-DDR1_BA2-PadD12)") (class "Default")
      (node (ref "U8") (pin "D12") (pinfunction "DDR1_BA2_D12") (pintype "passive+no_connect"))
    )
    (net (code "140") (name "unconnected-(U8D-DDR1_CASn-PadF9)") (class "Default")
      (node (ref "U8") (pin "F9") (pinfunction "DDR1_CASn_F9") (pintype "passive+no_connect"))
    )
    (net (code "141") (name "unconnected-(U8D-DDR1_DQ16-PadA19)") (class "Default")
      (node (ref "U8") (pin "A19") (pinfunction "DDR1_DQ16_A19") (pintype "passive+no_connect"))
    )
    (net (code "142") (name "unconnected-(U8D-DDR1_DQ17-PadB19)") (class "Default")
      (node (ref "U8") (pin "B19") (pinfunction "DDR1_DQ17_B19") (pintype "passive+no_connect"))
    )
    (net (code "143") (name "unconnected-(U8D-DDR1_ODT0-PadD11)") (class "Default")
      (node (ref "U8") (pin "D11") (pinfunction "DDR1_ODT0_D11") (pintype "passive+no_connect"))
    )
    (net (code "144") (name "unconnected-(U8D-DDR1_ODT1-PadE11)") (class "Default")
      (node (ref "U8") (pin "E11") (pinfunction "DDR1_ODT1_E11") (pintype "passive+no_connect"))
    )
    (net (code "145") (name "unconnected-(U8D-DDR1_PLL_TESTOUT_N-PadG14)") (class "Default")
      (node (ref "U8") (pin "G14") (pinfunction "DDR1_PLL_TESTOUT_N_G14") (pintype "passive+no_connect"))
    )
    (net (code "146") (name "unconnected-(U8D-DDR1_PLL_TESTOUT_P-PadF14)") (class "Default")
      (node (ref "U8") (pin "F14") (pinfunction "DDR1_PLL_TESTOUT_P_F14") (pintype "passive+no_connect"))
    )
    (net (code "147") (name "unconnected-(U8D-DDR1_PZQ-PadG15)") (class "Default")
      (node (ref "U8") (pin "G15") (pinfunction "DDR1_PZQ_G15") (pintype "passive+no_connect"))
    )
    (net (code "148") (name "unconnected-(U8D-DDR1_RASn-PadC6)") (class "Default")
      (node (ref "U8") (pin "C6") (pinfunction "DDR1_RASn_C6") (pintype "passive+no_connect"))
    )
    (net (code "149") (name "unconnected-(U8D-DDR1_WEn-PadF7)") (class "Default")
      (node (ref "U8") (pin "F7") (pinfunction "DDR1_WEn_F7") (pintype "passive+no_connect"))
    )
    (net (code "150") (name "unconnected-(U8E-DDR0_A3-PadG2)") (class "Default")
      (node (ref "U8") (pin "G2") (pinfunction "DDR0_A3_G2") (pintype "passive+no_connect"))
    )
    (net (code "151") (name "unconnected-(U8E-DDR0_A6-PadJ1)") (class "Default")
      (node (ref "U8") (pin "J1") (pinfunction "DDR0_A6_J1") (pintype "passive+no_connect"))
    )
    (net (code "152") (name "unconnected-(U8E-DDR0_A7-PadJ2)") (class "Default")
      (node (ref "U8") (pin "J2") (pinfunction "DDR0_A7_J2") (pintype "passive+no_connect"))
    )
    (net (code "153") (name "unconnected-(U8E-DDR0_A8-PadK2)") (class "Default")
      (node (ref "U8") (pin "K2") (pinfunction "DDR0_A8_K2") (pintype "passive+no_connect"))
    )
    (net (code "154") (name "unconnected-(U8E-DDR0_A9-PadK1)") (class "Default")
      (node (ref "U8") (pin "K1") (pinfunction "DDR0_A9_K1") (pintype "passive+no_connect"))
    )
    (net (code "155") (name "unconnected-(U8E-DDR0_A10-PadD1)") (class "Default")
      (node (ref "U8") (pin "D1") (pinfunction "DDR0_A10_D1") (pintype "passive+no_connect"))
    )
    (net (code "156") (name "unconnected-(U8E-DDR0_A11-PadE3)") (class "Default")
      (node (ref "U8") (pin "E3") (pinfunction "DDR0_A11_E3") (pintype "passive+no_connect"))
    )
    (net (code "157") (name "unconnected-(U8E-DDR0_A12-PadC1)") (class "Default")
      (node (ref "U8") (pin "C1") (pinfunction "DDR0_A12_C1") (pintype "passive+no_connect"))
    )
    (net (code "158") (name "unconnected-(U8E-DDR0_A13-PadD2)") (class "Default")
      (node (ref "U8") (pin "D2") (pinfunction "DDR0_A13_D2") (pintype "passive+no_connect"))
    )
    (net (code "159") (name "unconnected-(U8E-DDR0_A14-PadD3)") (class "Default")
      (node (ref "U8") (pin "D3") (pinfunction "DDR0_A14_D3") (pintype "passive+no_connect"))
    )
    (net (code "160") (name "unconnected-(U8E-DDR0_A15-PadH7)") (class "Default")
      (node (ref "U8") (pin "H7") (pinfunction "DDR0_A15_H7") (pintype "passive+no_connect"))
    )
    (net (code "161") (name "unconnected-(U8E-DDR0_ATB0-PadU6)") (class "Default")
      (node (ref "U8") (pin "U6") (pinfunction "DDR0_ATB0_U6") (pintype "passive+no_connect"))
    )
    (net (code "162") (name "unconnected-(U8E-DDR0_ATB1-PadU7)") (class "Default")
      (node (ref "U8") (pin "U7") (pinfunction "DDR0_ATB1_U7") (pintype "passive+no_connect"))
    )
    (net (code "163") (name "unconnected-(U8E-DDR0_BA0-PadC3)") (class "Default")
      (node (ref "U8") (pin "C3") (pinfunction "DDR0_BA0_C3") (pintype "passive+no_connect"))
    )
    (net (code "164") (name "unconnected-(U8E-DDR0_BA1-PadF4)") (class "Default")
      (node (ref "U8") (pin "F4") (pinfunction "DDR0_BA1_F4") (pintype "passive+no_connect"))
    )
    (net (code "165") (name "unconnected-(U8E-DDR0_BA2-PadM4)") (class "Default")
      (node (ref "U8") (pin "M4") (pinfunction "DDR0_BA2_M4") (pintype "passive+no_connect"))
    )
    (net (code "166") (name "unconnected-(U8E-DDR0_CASn-PadH6)") (class "Default")
      (node (ref "U8") (pin "H6") (pinfunction "DDR0_CASn_H6") (pintype "passive+no_connect"))
    )
    (net (code "167") (name "unconnected-(U8E-DDR0_DQ17-PadV2)") (class "Default")
      (node (ref "U8") (pin "V2") (pinfunction "DDR0_DQ17_V2") (pintype "passive+no_connect"))
    )
    (net (code "168") (name "unconnected-(U8E-DDR0_DQ19-PadU2)") (class "Default")
      (node (ref "U8") (pin "U2") (pinfunction "DDR0_DQ19_U2") (pintype "passive+no_connect"))
    )
    (net (code "169") (name "unconnected-(U8E-DDR0_ODT0-PadL4)") (class "Default")
      (node (ref "U8") (pin "L4") (pinfunction "DDR0_ODT0_L4") (pintype "passive+no_connect"))
    )
    (net (code "170") (name "unconnected-(U8E-DDR0_ODT1-PadL5)") (class "Default")
      (node (ref "U8") (pin "L5") (pinfunction "DDR0_ODT1_L5") (pintype "passive+no_connect"))
    )
    (net (code "171") (name "unconnected-(U8E-DDR0_PLL_TESTOUT_N-PadV7)") (class "Default")
      (node (ref "U8") (pin "V7") (pinfunction "DDR0_PLL_TESTOUT_N_V7") (pintype "passive+no_connect"))
    )
    (net (code "172") (name "unconnected-(U8E-DDR0_PLL_TESTOUT_P-PadV6)") (class "Default")
      (node (ref "U8") (pin "V6") (pinfunction "DDR0_PLL_TESTOUT_P_V6") (pintype "passive+no_connect"))
    )
    (net (code "173") (name "unconnected-(U8E-DDR0_RASn-PadF3)") (class "Default")
      (node (ref "U8") (pin "F3") (pinfunction "DDR0_RASn_F3") (pintype "passive+no_connect"))
    )
    (net (code "174") (name "unconnected-(U8E-DDR0_RESET-PadL7)") (class "Default")
      (node (ref "U8") (pin "L7") (pinfunction "DDR0_RESET_L7") (pintype "passive+no_connect"))
    )
    (net (code "175") (name "unconnected-(U8E-DDR0_WEn-PadG6)") (class "Default")
      (node (ref "U8") (pin "G6") (pinfunction "DDR0_WEn_G6") (pintype "passive+no_connect"))
    )
  )
)
